# moja-col.net
KiCad netlist of a schematic drawn in EAGLE
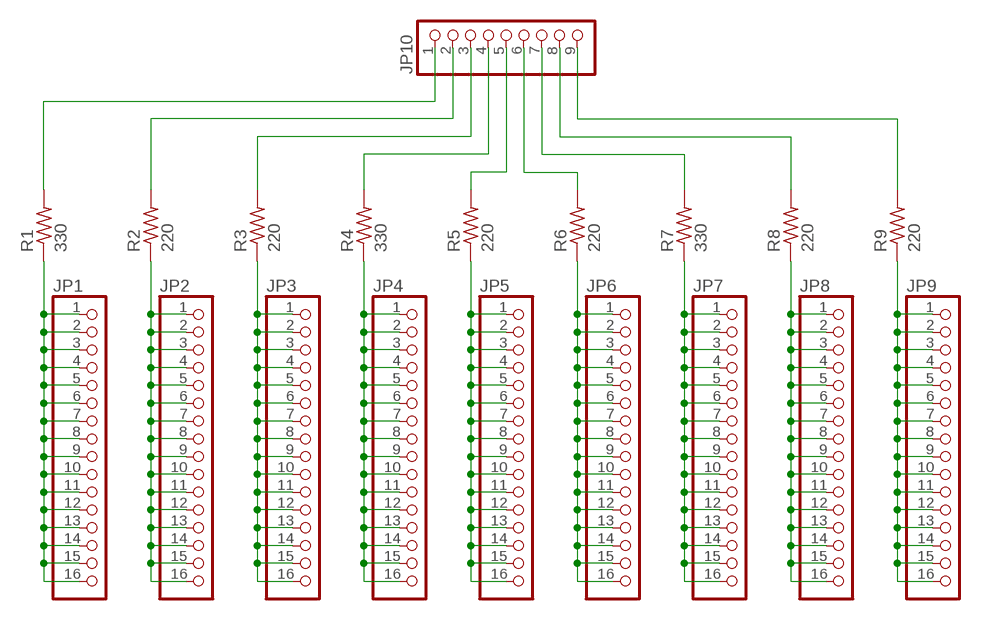
[diagram p0: schematic, sheet 1]

(export (version "E")
  (design (tool "Eeschema 10.0.6"))
  (components
    (comp (ref "JP1")
      (value "PINHD-1X16")
      (footprint "eagle-import:1X16")
      (libsource (lib "eagle-import") (part "PINHD-1X16"))
    )
    (comp (ref "JP2")
      (value "PINHD-1X16")
      (footprint "eagle-import:1X16")
      (libsource (lib "eagle-import") (part "PINHD-1X16"))
    )
    (comp (ref "JP3")
      (value "PINHD-1X16")
      (footprint "eagle-import:1X16")
      (libsource (lib "eagle-import") (part "PINHD-1X16"))
    )
    (comp (ref "JP4")
      (value "PINHD-1X16")
      (footprint "eagle-import:1X16")
      (libsource (lib "eagle-import") (part "PINHD-1X16"))
    )
    (comp (ref "JP5")
      (value "PINHD-1X16")
      (footprint "eagle-import:1X16")
      (libsource (lib "eagle-import") (part "PINHD-1X16"))
    )
    (comp (ref "JP6")
      (value "PINHD-1X16")
      (footprint "eagle-import:1X16")
      (libsource (lib "eagle-import") (part "PINHD-1X16"))
    )
    (comp (ref "JP7")
      (value "PINHD-1X16")
      (footprint "eagle-import:1X16")
      (libsource (lib "eagle-import") (part "PINHD-1X16"))
    )
    (comp (ref "JP8")
      (value "PINHD-1X16")
      (footprint "eagle-import:1X16")
      (libsource (lib "eagle-import") (part "PINHD-1X16"))
    )
    (comp (ref "JP9")
      (value "PINHD-1X16")
      (footprint "eagle-import:1X16")
      (libsource (lib "eagle-import") (part "PINHD-1X16"))
    )
    (comp (ref "JP10")
      (value "PINHD-1X9")
      (footprint "eagle-import:1X09")
      (libsource (lib "eagle-import") (part "PINHD-1X9"))
    )
    (comp (ref "R1")
      (value "330")
      (footprint "eagle-import:0204V")
      (libsource (lib "eagle-import") (part "R-US_0204/2V"))
    )
    (comp (ref "R2")
      (value "220")
      (footprint "eagle-import:0204V")
      (libsource (lib "eagle-import") (part "R-US_0204/2V"))
    )
    (comp (ref "R3")
      (value "220")
      (footprint "eagle-import:0204V")
      (libsource (lib "eagle-import") (part "R-US_0204/2V"))
    )
    (comp (ref "R4")
      (value "330")
      (footprint "eagle-import:0204V")
      (libsource (lib "eagle-import") (part "R-US_0204/2V"))
    )
    (comp (ref "R5")
      (value "220")
      (footprint "eagle-import:0204V")
      (libsource (lib "eagle-import") (part "R-US_0204/2V"))
    )
    (comp (ref "R6")
      (value "220")
      (footprint "eagle-import:0204V")
      (libsource (lib "eagle-import") (part "R-US_0204/2V"))
    )
    (comp (ref "R7")
      (value "330")
      (footprint "eagle-import:0204V")
      (libsource (lib "eagle-import") (part "R-US_0204/2V"))
    )
    (comp (ref "R8")
      (value "220")
      (footprint "eagle-import:0204V")
      (libsource (lib "eagle-import") (part "R-US_0204/2V"))
    )
    (comp (ref "R9")
      (value "220")
      (footprint "eagle-import:0204V")
      (libsource (lib "eagle-import") (part "R-US_0204/2V"))
    )
  )
  (nets
    (net (code "1") (name "Net-(JP1-Pad1)") (class "Default")
      (node (ref "JP1") (pin "1") (pinfunction "1_1") (pintype "passive"))
      (node (ref "JP1") (pin "10") (pinfunction "10_10") (pintype "passive"))
      (node (ref "JP1") (pin "11") (pinfunction "11_11") (pintype "passive"))
      (node (ref "JP1") (pin "12") (pinfunction "12_12") (pintype "passive"))
      (node (ref "JP1") (pin "13") (pinfunction "13_13") (pintype "passive"))
      (node (ref "JP1") (pin "14") (pinfunction "14_14") (pintype "passive"))
      (node (ref "JP1") (pin "15") (pinfunction "15_15") (pintype "passive"))
      (node (ref "JP1") (pin "16") (pinfunction "16_16") (pintype "passive"))
      (node (ref "JP1") (pin "2") (pinfunction "2_2") (pintype "passive"))
      (node (ref "JP1") (pin "3") (pinfunction "3_3") (pintype "passive"))
      (node (ref "JP1") (pin "4") (pinfunction "4_4") (pintype "passive"))
      (node (ref "JP1") (pin "5") (pinfunction "5_5") (pintype "passive"))
      (node (ref "JP1") (pin "6") (pinfunction "6_6") (pintype "passive"))
      (node (ref "JP1") (pin "7") (pinfunction "7_7") (pintype "passive"))
      (node (ref "JP1") (pin "8") (pinfunction "8_8") (pintype "passive"))
      (node (ref "JP1") (pin "9") (pinfunction "9_9") (pintype "passive"))
      (node (ref "R1") (pin "1") (pinfunction "1_1") (pintype "passive"))
    )
    (net (code "2") (name "Net-(JP2-Pad1)") (class "Default")
      (node (ref "JP2") (pin "1") (pinfunction "1_1") (pintype "passive"))
      (node (ref "JP2") (pin "10") (pinfunction "10_10") (pintype "passive"))
      (node (ref "JP2") (pin "11") (pinfunction "11_11") (pintype "passive"))
      (node (ref "JP2") (pin "12") (pinfunction "12_12") (pintype "passive"))
      (node (ref "JP2") (pin "13") (pinfunction "13_13") (pintype "passive"))
      (node (ref "JP2") (pin "14") (pinfunction "14_14") (pintype "passive"))
      (node (ref "JP2") (pin "15") (pinfunction "15_15") (pintype "passive"))
      (node (ref "JP2") (pin "16") (pinfunction "16_16") (pintype "passive"))
      (node (ref "JP2") (pin "2") (pinfunction "2_2") (pintype "passive"))
      (node (ref "JP2") (pin "3") (pinfunction "3_3") (pintype "passive"))
      (node (ref "JP2") (pin "4") (pinfunction "4_4") (pintype "passive"))
      (node (ref "JP2") (pin "5") (pinfunction "5_5") (pintype "passive"))
      (node (ref "JP2") (pin "6") (pinfunction "6_6") (pintype "passive"))
      (node (ref "JP2") (pin "7") (pinfunction "7_7") (pintype "passive"))
      (node (ref "JP2") (pin "8") (pinfunction "8_8") (pintype "passive"))
      (node (ref "JP2") (pin "9") (pinfunction "9_9") (pintype "passive"))
      (node (ref "R2") (pin "1") (pinfunction "1_1") (pintype "passive"))
    )
    (net (code "3") (name "Net-(JP3-Pad1)") (class "Default")
      (node (ref "JP3") (pin "1") (pinfunction "1_1") (pintype "passive"))
      (node (ref "JP3") (pin "10") (pinfunction "10_10") (pintype "passive"))
      (node (ref "JP3") (pin "11") (pinfunction "11_11") (pintype "passive"))
      (node (ref "JP3") (pin "12") (pinfunction "12_12") (pintype "passive"))
      (node (ref "JP3") (pin "13") (pinfunction "13_13") (pintype "passive"))
      (node (ref "JP3") (pin "14") (pinfunction "14_14") (pintype "passive"))
      (node (ref "JP3") (pin "15") (pinfunction "15_15") (pintype "passive"))
      (node (ref "JP3") (pin "16") (pinfunction "16_16") (pintype "passive"))
      (node (ref "JP3") (pin "2") (pinfunction "2_2") (pintype "passive"))
      (node (ref "JP3") (pin "3") (pinfunction "3_3") (pintype "passive"))
      (node (ref "JP3") (pin "4") (pinfunction "4_4") (pintype "passive"))
      (node (ref "JP3") (pin "5") (pinfunction "5_5") (pintype "passive"))
      (node (ref "JP3") (pin "6") (pinfunction "6_6") (pintype "passive"))
      (node (ref "JP3") (pin "7") (pinfunction "7_7") (pintype "passive"))
      (node (ref "JP3") (pin "8") (pinfunction "8_8") (pintype "passive"))
      (node (ref "JP3") (pin "9") (pinfunction "9_9") (pintype "passive"))
      (node (ref "R3") (pin "1") (pinfunction "1_1") (pintype "passive"))
    )
    (net (code "4") (name "Net-(JP4-Pad1)") (class "Default")
      (node (ref "JP4") (pin "1") (pinfunction "1_1") (pintype "passive"))
      (node (ref "JP4") (pin "10") (pinfunction "10_10") (pintype "passive"))
      (node (ref "JP4") (pin "11") (pinfunction "11_11") (pintype "passive"))
      (node (ref "JP4") (pin "12") (pinfunction "12_12") (pintype "passive"))
      (node (ref "JP4") (pin "13") (pinfunction "13_13") (pintype "passive"))
      (node (ref "JP4") (pin "14") (pinfunction "14_14") (pintype "passive"))
      (node (ref "JP4") (pin "15") (pinfunction "15_15") (pintype "passive"))
      (node (ref "JP4") (pin "16") (pinfunction "16_16") (pintype "passive"))
      (node (ref "JP4") (pin "2") (pinfunction "2_2") (pintype "passive"))
      (node (ref "JP4") (pin "3") (pinfunction "3_3") (pintype "passive"))
      (node (ref "JP4") (pin "4") (pinfunction "4_4") (pintype "passive"))
      (node (ref "JP4") (pin "5") (pinfunction "5_5") (pintype "passive"))
      (node (ref "JP4") (pin "6") (pinfunction "6_6") (pintype "passive"))
      (node (ref "JP4") (pin "7") (pinfunction "7_7") (pintype "passive"))
      (node (ref "JP4") (pin "8") (pinfunction "8_8") (pintype "passive"))
      (node (ref "JP4") (pin "9") (pinfunction "9_9") (pintype "passive"))
      (node (ref "R4") (pin "1") (pinfunction "1_1") (pintype "passive"))
    )
    (net (code "5") (name "Net-(JP5-Pad1)") (class "Default")
      (node (ref "JP5") (pin "1") (pinfunction "1_1") (pintype "passive"))
      (node (ref "JP5") (pin "10") (pinfunction "10_10") (pintype "passive"))
      (node (ref "JP5") (pin "11") (pinfunction "11_11") (pintype "passive"))
      (node (ref "JP5") (pin "12") (pinfunction "12_12") (pintype "passive"))
      (node (ref "JP5") (pin "13") (pinfunction "13_13") (pintype "passive"))
      (node (ref "JP5") (pin "14") (pinfunction "14_14") (pintype "passive"))
      (node (ref "JP5") (pin "15") (pinfunction "15_15") (pintype "passive"))
      (node (ref "JP5") (pin "16") (pinfunction "16_16") (pintype "passive"))
      (node (ref "JP5") (pin "2") (pinfunction "2_2") (pintype "passive"))
      (node (ref "JP5") (pin "3") (pinfunction "3_3") (pintype "passive"))
      (node (ref "JP5") (pin "4") (pinfunction "4_4") (pintype "passive"))
      (node (ref "JP5") (pin "5") (pinfunction "5_5") (pintype "passive"))
      (node (ref "JP5") (pin "6") (pinfunction "6_6") (pintype "passive"))
      (node (ref "JP5") (pin "7") (pinfunction "7_7") (pintype "passive"))
      (node (ref "JP5") (pin "8") (pinfunction "8_8") (pintype "passive"))
      (node (ref "JP5") (pin "9") (pinfunction "9_9") (pintype "passive"))
      (node (ref "R5") (pin "1") (pinfunction "1_1") (pintype "passive"))
    )
    (net (code "6") (name "Net-(JP6-Pad1)") (class "Default")
      (node (ref "JP6") (pin "1") (pinfunction "1_1") (pintype "passive"))
      (node (ref "JP6") (pin "10") (pinfunction "10_10") (pintype "passive"))
      (node (ref "JP6") (pin "11") (pinfunction "11_11") (pintype "passive"))
      (node (ref "JP6") (pin "12") (pinfunction "12_12") (pintype "passive"))
      (node (ref "JP6") (pin "13") (pinfunction "13_13") (pintype "passive"))
      (node (ref "JP6") (pin "14") (pinfunction "14_14") (pintype "passive"))
      (node (ref "JP6") (pin "15") (pinfunction "15_15") (pintype "passive"))
      (node (ref "JP6") (pin "16") (pinfunction "16_16") (pintype "passive"))
      (node (ref "JP6") (pin "2") (pinfunction "2_2") (pintype "passive"))
      (node (ref "JP6") (pin "3") (pinfunction "3_3") (pintype "passive"))
      (node (ref "JP6") (pin "4") (pinfunction "4_4") (pintype "passive"))
      (node (ref "JP6") (pin "5") (pinfunction "5_5") (pintype "passive"))
      (node (ref "JP6") (pin "6") (pinfunction "6_6") (pintype "passive"))
      (node (ref "JP6") (pin "7") (pinfunction "7_7") (pintype "passive"))
      (node (ref "JP6") (pin "8") (pinfunction "8_8") (pintype "passive"))
      (node (ref "JP6") (pin "9") (pinfunction "9_9") (pintype "passive"))
      (node (ref "R6") (pin "1") (pinfunction "1_1") (pintype "passive"))
    )
    (net (code "7") (name "Net-(JP7-Pad1)") (class "Default")
      (node (ref "JP7") (pin "1") (pinfunction "1_1") (pintype "passive"))
      (node (ref "JP7") (pin "10") (pinfunction "10_10") (pintype "passive"))
      (node (ref "JP7") (pin "11") (pinfunction "11_11") (pintype "passive"))
      (node (ref "JP7") (pin "12") (pinfunction "12_12") (pintype "passive"))
      (node (ref "JP7") (pin "13") (pinfunction "13_13") (pintype "passive"))
      (node (ref "JP7") (pin "14") (pinfunction "14_14") (pintype "passive"))
      (node (ref "JP7") (pin "15") (pinfunction "15_15") (pintype "passive"))
      (node (ref "JP7") (pin "16") (pinfunction "16_16") (pintype "passive"))
      (node (ref "JP7") (pin "2") (pinfunction "2_2") (pintype "passive"))
      (node (ref "JP7") (pin "3") (pinfunction "3_3") (pintype "passive"))
      (node (ref "JP7") (pin "4") (pinfunction "4_4") (pintype "passive"))
      (node (ref "JP7") (pin "5") (pinfunction "5_5") (pintype "passive"))
      (node (ref "JP7") (pin "6") (pinfunction "6_6") (pintype "passive"))
      (node (ref "JP7") (pin "7") (pinfunction "7_7") (pintype "passive"))
      (node (ref "JP7") (pin "8") (pinfunction "8_8") (pintype "passive"))
      (node (ref "JP7") (pin "9") (pinfunction "9_9") (pintype "passive"))
      (node (ref "R7") (pin "1") (pinfunction "1_1") (pintype "passive"))
    )
    (net (code "8") (name "Net-(JP8-Pad1)") (class "Default")
      (node (ref "JP8") (pin "1") (pinfunction "1_1") (pintype "passive"))
      (node (ref "JP8") (pin "10") (pinfunction "10_10") (pintype "passive"))
      (node (ref "JP8") (pin "11") (pinfunction "11_11") (pintype "passive"))
      (node (ref "JP8") (pin "12") (pinfunction "12_12") (pintype "passive"))
      (node (ref "JP8") (pin "13") (pinfunction "13_13") (pintype "passive"))
      (node (ref "JP8") (pin "14") (pinfunction "14_14") (pintype "passive"))
      (node (ref "JP8") (pin "15") (pinfunction "15_15") (pintype "passive"))
      (node (ref "JP8") (pin "16") (pinfunction "16_16") (pintype "passive"))
      (node (ref "JP8") (pin "2") (pinfunction "2_2") (pintype "passive"))
      (node (ref "JP8") (pin "3") (pinfunction "3_3") (pintype "passive"))
      (node (ref "JP8") (pin "4") (pinfunction "4_4") (pintype "passive"))
      (node (ref "JP8") (pin "5") (pinfunction "5_5") (pintype "passive"))
      (node (ref "JP8") (pin "6") (pinfunction "6_6") (pintype "passive"))
      (node (ref "JP8") (pin "7") (pinfunction "7_7") (pintype "passive"))
      (node (ref "JP8") (pin "8") (pinfunction "8_8") (pintype "passive"))
      (node (ref "JP8") (pin "9") (pinfunction "9_9") (pintype "passive"))
      (node (ref "R8") (pin "1") (pinfunction "1_1") (pintype "passive"))
    )
    (net (code "9") (name "Net-(JP9-Pad1)") (class "Default")
      (node (ref "JP9") (pin "1") (pinfunction "1_1") (pintype "passive"))
      (node (ref "JP9") (pin "10") (pinfunction "10_10") (pintype "passive"))
      (node (ref "JP9") (pin "11") (pinfunction "11_11") (pintype "passive"))
      (node (ref "JP9") (pin "12") (pinfunction "12_12") (pintype "passive"))
      (node (ref "JP9") (pin "13") (pinfunction "13_13") (pintype "passive"))
      (node (ref "JP9") (pin "14") (pinfunction "14_14") (pintype "passive"))
      (node (ref "JP9") (pin "15") (pinfunction "15_15") (pintype "passive"))
      (node (ref "JP9") (pin "16") (pinfunction "16_16") (pintype "passive"))
      (node (ref "JP9") (pin "2") (pinfunction "2_2") (pintype "passive"))
      (node (ref "JP9") (pin "3") (pinfunction "3_3") (pintype "passive"))
      (node (ref "JP9") (pin "4") (pinfunction "4_4") (pintype "passive"))
      (node (ref "JP9") (pin "5") (pinfunction "5_5") (pintype "passive"))
      (node (ref "JP9") (pin "6") (pinfunction "6_6") (pintype "passive"))
      (node (ref "JP9") (pin "7") (pinfunction "7_7") (pintype "passive"))
      (node (ref "JP9") (pin "8") (pinfunction "8_8") (pintype "passive"))
      (node (ref "JP9") (pin "9") (pinfunction "9_9") (pintype "passive"))
      (node (ref "R9") (pin "1") (pinfunction "1_1") (pintype "passive"))
    )
    (net (code "10") (name "Net-(JP10-Pad1)") (class "Default")
      (node (ref "JP10") (pin "1") (pinfunction "1_1") (pintype "passive"))
      (node (ref "R1") (pin "2") (pinfunction "2_2") (pintype "passive"))
    )
    (net (code "11") (name "Net-(JP10-Pad2)") (class "Default")
      (node (ref "JP10") (pin "2") (pinfunction "2_2") (pintype "passive"))
      (node (ref "R2") (pin "2") (pinfunction "2_2") (pintype "passive"))
    )
    (net (code "12") (name "Net-(JP10-Pad3)") (class "Default")
      (node (ref "JP10") (pin "3") (pinfunction "3_3") (pintype "passive"))
      (node (ref "R3") (pin "2") (pinfunction "2_2") (pintype "passive"))
    )
    (net (code "13") (name "Net-(JP10-Pad4)") (class "Default")
      (node (ref "JP10") (pin "4") (pinfunction "4_4") (pintype "passive"))
      (node (ref "R4") (pin "2") (pinfunction "2_2") (pintype "passive"))
    )
    (net (code "14") (name "Net-(JP10-Pad5)") (class "Default")
      (node (ref "JP10") (pin "5") (pinfunction "5_5") (pintype "passive"))
      (node (ref "R5") (pin "2") (pinfunction "2_2") (pintype "passive"))
    )
    (net (code "15") (name "Net-(JP10-Pad6)") (class "Default")
      (node (ref "JP10") (pin "6") (pinfunction "6_6") (pintype "passive"))
      (node (ref "R6") (pin "2") (pinfunction "2_2") (pintype "passive"))
    )
    (net (code "16") (name "Net-(JP10-Pad7)") (class "Default")
      (node (ref "JP10") (pin "7") (pinfunction "7_7") (pintype "passive"))
      (node (ref "R7") (pin "2") (pinfunction "2_2") (pintype "passive"))
    )
    (net (code "17") (name "Net-(JP10-Pad8)") (class "Default")
      (node (ref "JP10") (pin "8") (pinfunction "8_8") (pintype "passive"))
      (node (ref "R8") (pin "2") (pinfunction "2_2") (pintype "passive"))
    )
    (net (code "18") (name "Net-(JP10-Pad9)") (class "Default")
      (node (ref "JP10") (pin "9") (pinfunction "9_9") (pintype "passive"))
      (node (ref "R9") (pin "2") (pinfunction "2_2") (pintype "passive"))
    )
  )
)
